# Microduino_v0_1.net
KiCad netlist of a schematic drawn in EAGLE
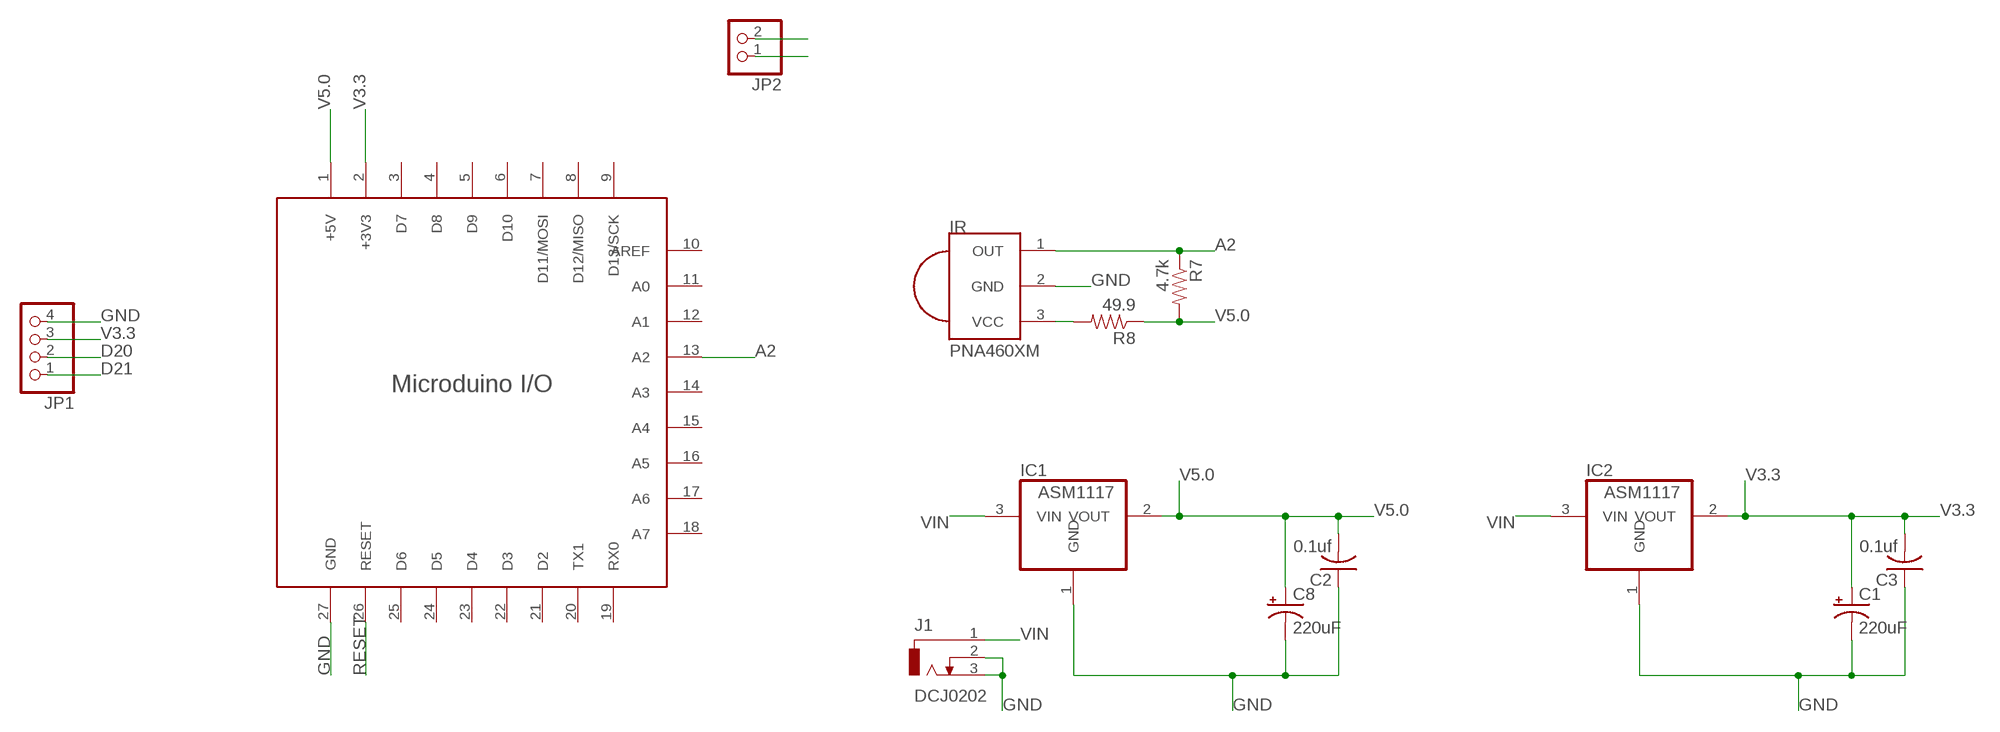
[diagram p0: schematic, sheet 1]

(export (version "E")
  (design (tool "Eeschema 10.0.6"))
  (components
    (comp (ref "C1")
      (value "220uF")
      (footprint "eagle-import:E2,5-5")
      (libsource (lib "eagle-import") (part "CPOL-USE2.5-5"))
    )
    (comp (ref "C2")
      (value "0.1uf")
      (footprint "eagle-import:C025-024X044")
      (libsource (lib "eagle-import") (part "C-US025-024X044"))
    )
    (comp (ref "C3")
      (value "0.1uf")
      (footprint "eagle-import:C025-024X044")
      (libsource (lib "eagle-import") (part "C-US025-024X044"))
    )
    (comp (ref "C8")
      (value "220uF")
      (footprint "eagle-import:E2,5-5")
      (libsource (lib "eagle-import") (part "CPOL-USE2.5-5"))
    )
    (comp (ref "IC1")
      (value "ASM1117")
      (footprint "eagle-import:SOT223")
      (fields (field (name "MPN") "REG1117"))
      (libsource (lib "eagle-import") (part "REG1117"))
    )
    (comp (ref "IC2")
      (value "ASM1117")
      (footprint "eagle-import:SOT223")
      (fields (field (name "MPN") "REG1117"))
      (libsource (lib "eagle-import") (part "REG1117"))
    )
    (comp (ref "IR")
      (value "PNA460XM")
      (footprint "eagle-import:PNA460XM")
      (libsource (lib "eagle-import") (part "PNA460XM"))
    )
    (comp (ref "J1")
      (value "DCJ0202")
      (footprint "eagle-import:DCJ0202")
      (libsource (lib "eagle-import") (part "DCJ0202"))
    )
    (comp (ref "JP1")
      (value "PINHD-1X4")
      (footprint "eagle-import:1X04")
      (libsource (lib "eagle-import") (part "PINHD-1X4"))
    )
    (comp (ref "JP2")
      (value "PINHD-1X2")
      (footprint "eagle-import:1X02")
      (libsource (lib "eagle-import") (part "PINHD-1X2"))
    )
    (comp (ref "R7")
      (value "4.7k")
      (footprint "eagle-import:AXIAL-0.3")
      (libsource (lib "eagle-import") (part "RESISTORPTH1"))
    )
    (comp (ref "R8")
      (value "49.9")
      (footprint "eagle-import:AXIAL-0.3")
      (libsource (lib "eagle-import") (part "RESISTORPTH1"))
    )
    (comp (ref "U$1")
      (value "PING-MICRDUINO-DZ/1009")
      (footprint "eagle-import:PIN-MICRODUINO-1009")
      (libsource (lib "eagle-import") (part "PING-MICRDUINO-DZ/1009"))
    )
  )
  (nets
    (net (code "1") (name "/A2") (class "Default")
      (node (ref "IR") (pin "1") (pinfunction "OUT_1") (pintype "output"))
      (node (ref "R7") (pin "P$1") (pinfunction "1_P$1") (pintype "passive"))
      (node (ref "U$1") (pin "13") (pinfunction "A2_13") (pintype "bidirectional"))
    )
    (net (code "2") (name "/D20") (class "Default")
      (node (ref "JP1") (pin "2") (pinfunction "2_2") (pintype "passive"))
      (node (ref "JP2") (pin "2") (pinfunction "2_2") (pintype "passive"))
    )
    (net (code "3") (name "/D21") (class "Default")
      (node (ref "JP1") (pin "1") (pinfunction "1_1") (pintype "passive"))
      (node (ref "JP2") (pin "1") (pinfunction "1_1") (pintype "passive"))
    )
    (net (code "4") (name "/GND") (class "Default")
      (node (ref "C1") (pin "-") (pinfunction "-_-") (pintype "passive"))
      (node (ref "C2") (pin "1") (pinfunction "1_1") (pintype "passive"))
      (node (ref "C3") (pin "1") (pinfunction "1_1") (pintype "passive"))
      (node (ref "C8") (pin "-") (pinfunction "-_-") (pintype "passive"))
      (node (ref "IC1") (pin "1") (pinfunction "GND_1") (pintype "power_in"))
      (node (ref "IC2") (pin "1") (pinfunction "GND_1") (pintype "power_in"))
      (node (ref "IR") (pin "2") (pinfunction "GND_2") (pintype "power_in"))
      (node (ref "J1") (pin "2") (pinfunction "2_2") (pintype "passive"))
      (node (ref "J1") (pin "3") (pinfunction "3_3") (pintype "passive"))
      (node (ref "JP1") (pin "4") (pinfunction "4_4") (pintype "passive"))
      (node (ref "U$1") (pin "27") (pinfunction "GND_27") (pintype "bidirectional"))
    )
    (net (code "5") (name "/RESET") (class "Default")
      (node (ref "U$1") (pin "26") (pinfunction "RESET_26") (pintype "bidirectional"))
    )
    (net (code "6") (name "/V3.3") (class "Default")
      (node (ref "C1") (pin "+") (pinfunction "+_+") (pintype "passive"))
      (node (ref "C3") (pin "2") (pinfunction "2_2") (pintype "passive"))
      (node (ref "IC2") (pin "2") (pinfunction "VOUT_2") (pintype "output"))
      (node (ref "JP1") (pin "3") (pinfunction "3_3") (pintype "passive"))
      (node (ref "U$1") (pin "2") (pinfunction "+3V3_2") (pintype "bidirectional"))
    )
    (net (code "7") (name "/V5.0") (class "Default")
      (node (ref "C2") (pin "2") (pinfunction "2_2") (pintype "passive"))
      (node (ref "C8") (pin "+") (pinfunction "+_+") (pintype "passive"))
      (node (ref "IC1") (pin "2") (pinfunction "VOUT_2") (pintype "output"))
      (node (ref "R7") (pin "P$2") (pinfunction "2_P$2") (pintype "passive"))
      (node (ref "R8") (pin "P$1") (pinfunction "1_P$1") (pintype "passive"))
      (node (ref "U$1") (pin "1") (pinfunction "+5V_1") (pintype "bidirectional"))
    )
    (net (code "8") (name "/VIN") (class "Default")
      (node (ref "IC1") (pin "3") (pinfunction "VIN_3") (pintype "input"))
      (node (ref "IC2") (pin "3") (pinfunction "VIN_3") (pintype "input"))
      (node (ref "J1") (pin "1") (pinfunction "1_1") (pintype "passive"))
    )
    (net (code "9") (name "Net-(IR-VCC)") (class "Default")
      (node (ref "IR") (pin "3") (pinfunction "VCC_3") (pintype "power_in"))
      (node (ref "R8") (pin "P$2") (pinfunction "2_P$2") (pintype "passive"))
    )
    (net (code "10") (name "unconnected-(U$1-A0-Pad11)") (class "Default")
      (node (ref "U$1") (pin "11") (pinfunction "A0_11") (pintype "bidirectional"))
    )
    (net (code "11") (name "unconnected-(U$1-A1-Pad12)") (class "Default")
      (node (ref "U$1") (pin "12") (pinfunction "A1_12") (pintype "bidirectional"))
    )
    (net (code "12") (name "unconnected-(U$1-A3-Pad14)") (class "Default")
      (node (ref "U$1") (pin "14") (pinfunction "A3_14") (pintype "bidirectional"))
    )
    (net (code "13") (name "unconnected-(U$1-A4-Pad15)") (class "Default")
      (node (ref "U$1") (pin "15") (pinfunction "A4_15") (pintype "bidirectional"))
    )
    (net (code "14") (name "unconnected-(U$1-A5-Pad16)") (class "Default")
      (node (ref "U$1") (pin "16") (pinfunction "A5_16") (pintype "bidirectional"))
    )
    (net (code "15") (name "unconnected-(U$1-A6-Pad17)") (class "Default")
      (node (ref "U$1") (pin "17") (pinfunction "A6_17") (pintype "bidirectional"))
    )
    (net (code "16") (name "unconnected-(U$1-A7-Pad18)") (class "Default")
      (node (ref "U$1") (pin "18") (pinfunction "A7_18") (pintype "bidirectional"))
    )
    (net (code "17") (name "unconnected-(U$1-AREF-Pad10)") (class "Default")
      (node (ref "U$1") (pin "10") (pinfunction "AREF_10") (pintype "bidirectional"))
    )
    (net (code "18") (name "unconnected-(U$1-D2-Pad21)") (class "Default")
      (node (ref "U$1") (pin "21") (pinfunction "D2_21") (pintype "bidirectional"))
    )
    (net (code "19") (name "unconnected-(U$1-D3-Pad22)") (class "Default")
      (node (ref "U$1") (pin "22") (pinfunction "D3_22") (pintype "bidirectional"))
    )
    (net (code "20") (name "unconnected-(U$1-D4-Pad23)") (class "Default")
      (node (ref "U$1") (pin "23") (pinfunction "D4_23") (pintype "bidirectional"))
    )
    (net (code "21") (name "unconnected-(U$1-D5-Pad24)") (class "Default")
      (node (ref "U$1") (pin "24") (pinfunction "D5_24") (pintype "bidirectional"))
    )
    (net (code "22") (name "unconnected-(U$1-D6-Pad25)") (class "Default")
      (node (ref "U$1") (pin "25") (pinfunction "D6_25") (pintype "bidirectional"))
    )
    (net (code "23") (name "unconnected-(U$1-D7-Pad3)") (class "Default")
      (node (ref "U$1") (pin "3") (pinfunction "D7_3") (pintype "bidirectional"))
    )
    (net (code "24") (name "unconnected-(U$1-D8-Pad4)") (class "Default")
      (node (ref "U$1") (pin "4") (pinfunction "D8_4") (pintype "bidirectional"))
    )
    (net (code "25") (name "unconnected-(U$1-D9-Pad5)") (class "Default")
      (node (ref "U$1") (pin "5") (pinfunction "D9_5") (pintype "bidirectional"))
    )
    (net (code "26") (name "unconnected-(U$1-D10-Pad6)") (class "Default")
      (node (ref "U$1") (pin "6") (pinfunction "D10_6") (pintype "bidirectional"))
    )
    (net (code "27") (name "unconnected-(U$1-D11{slash}MOSI-Pad7)") (class "Default")
      (node (ref "U$1") (pin "7") (pinfunction "D11/MOSI_7") (pintype "bidirectional"))
    )
    (net (code "28") (name "unconnected-(U$1-D12{slash}MISO-Pad8)") (class "Default")
      (node (ref "U$1") (pin "8") (pinfunction "D12/MISO_8") (pintype "bidirectional"))
    )
    (net (code "29") (name "unconnected-(U$1-D13{slash}SCK-Pad9)") (class "Default")
      (node (ref "U$1") (pin "9") (pinfunction "D13/SCK_9") (pintype "bidirectional"))
    )
    (net (code "30") (name "unconnected-(U$1-RX0-Pad19)") (class "Default")
      (node (ref "U$1") (pin "19") (pinfunction "RX0_19") (pintype "bidirectional"))
    )
    (net (code "31") (name "unconnected-(U$1-TX1-Pad20)") (class "Default")
      (node (ref "U$1") (pin "20") (pinfunction "TX1_20") (pintype "bidirectional"))
    )
  )
)
